# 13_-TYPEC0_PROG.net
KiCad netlist of a schematic drawn in Altium Designer
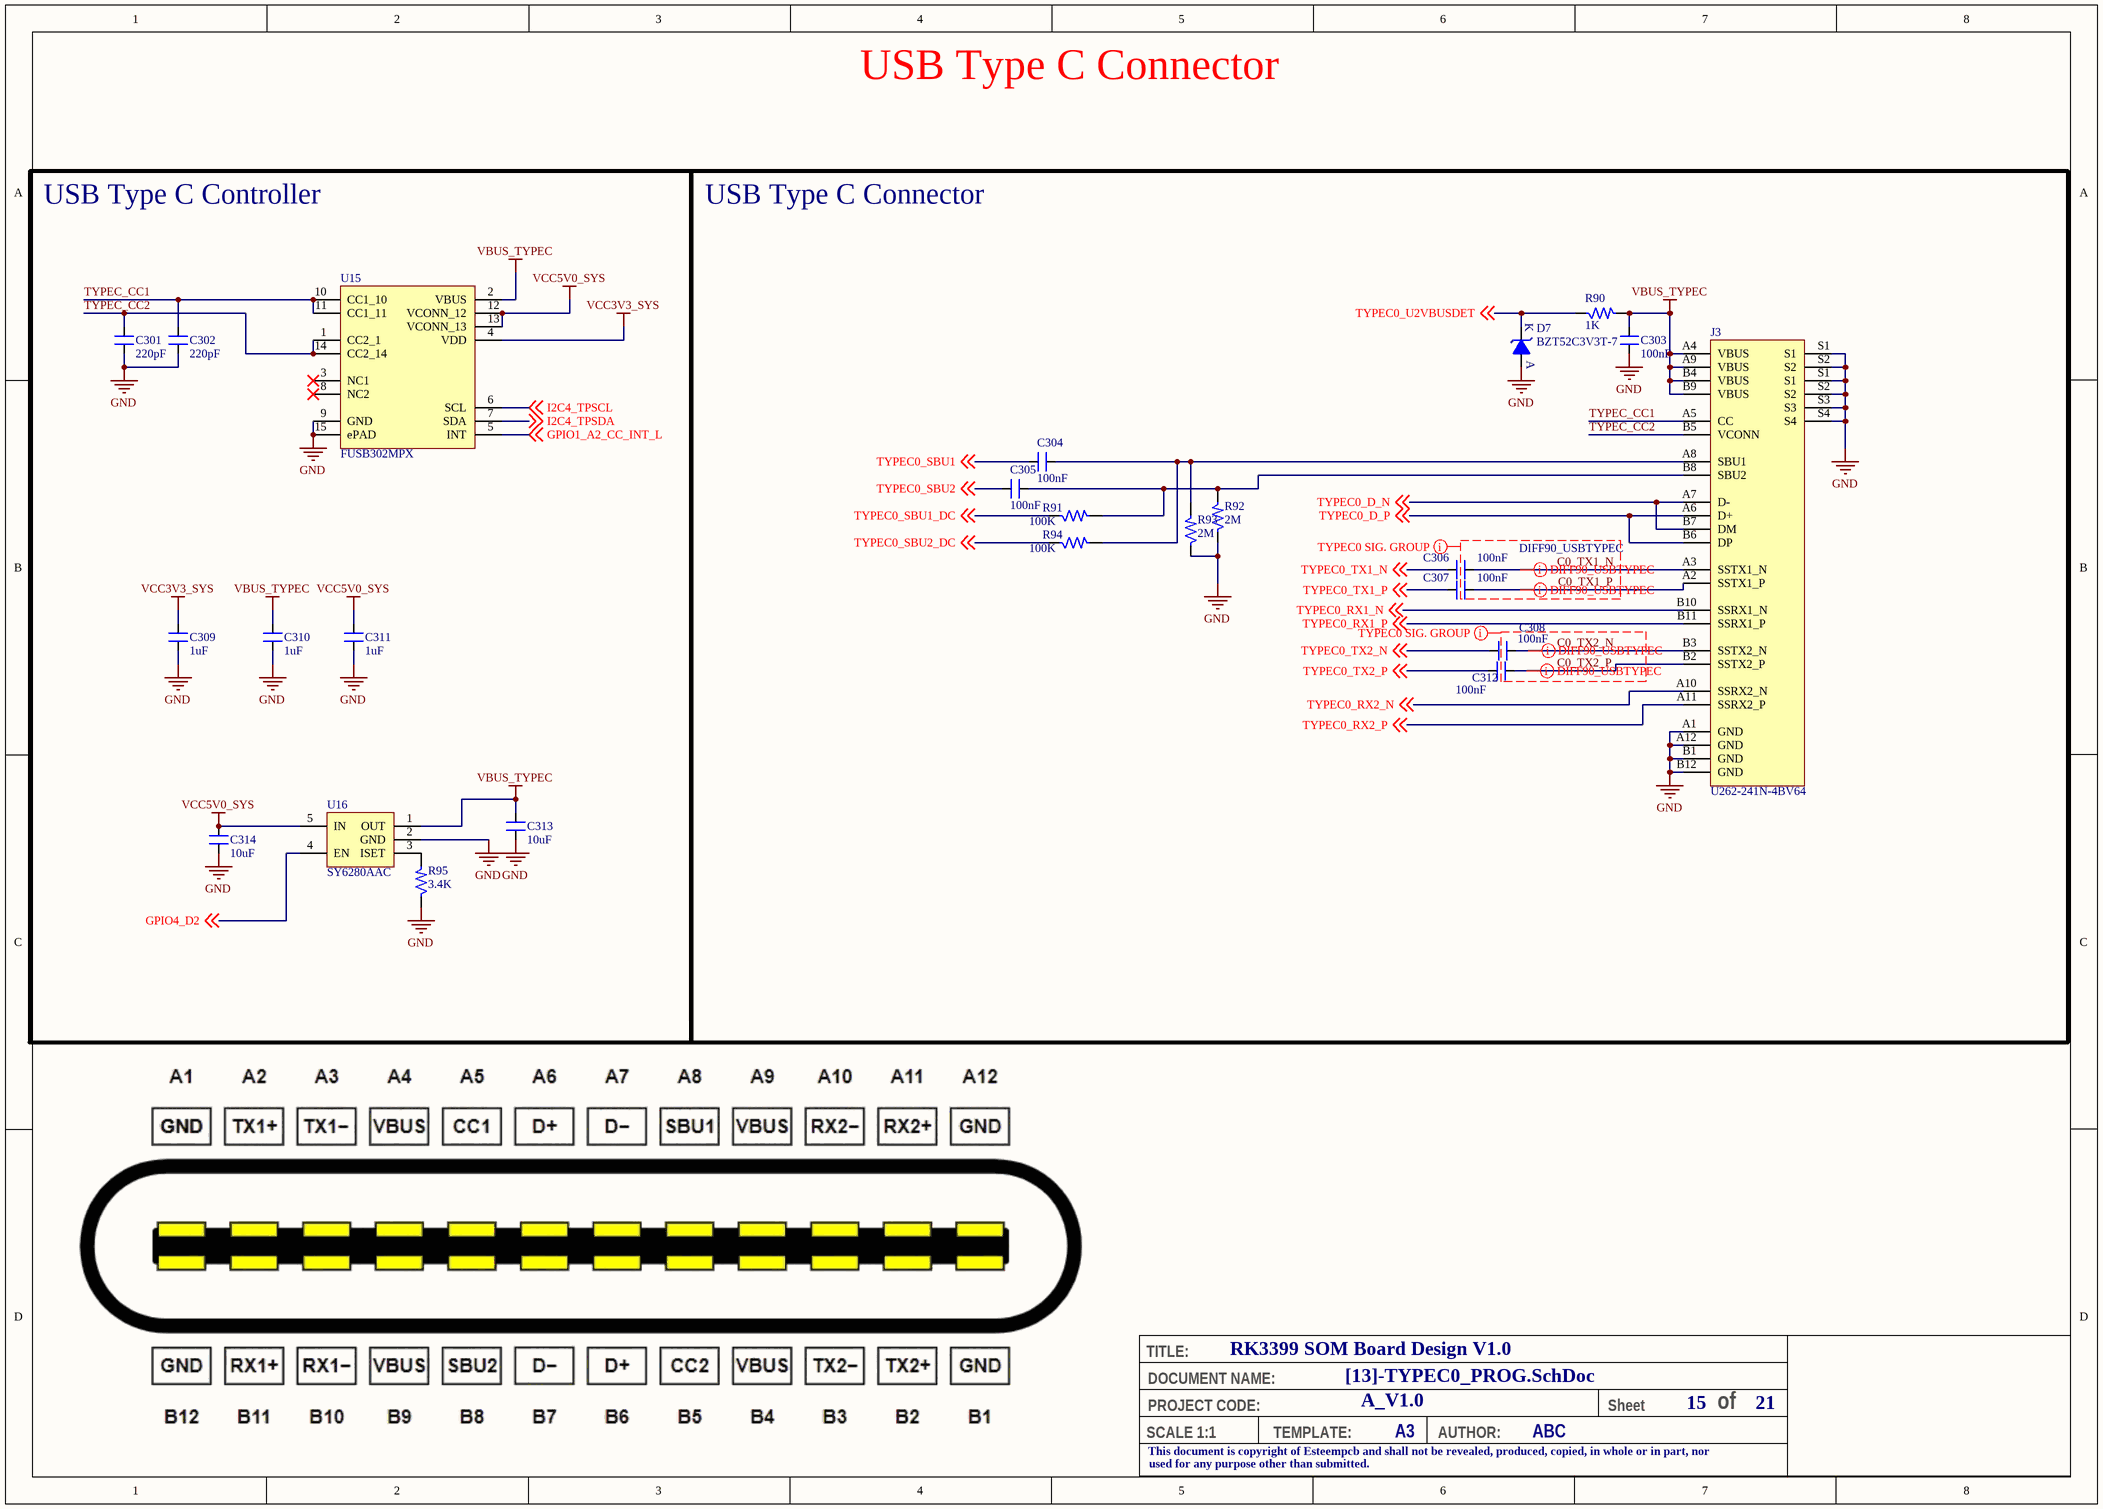
[diagram p0: [13]-TYPEC0_PROG.SchDoc]

(export (version "E")
  (design (tool "Eeschema 10.0.6"))
  (components
    (comp (ref "C301")
      (value "220pF")
      (footprint "CAP_0402")
      (description "220pF ±10% 10V Ceramic Capacitor X7R 0402 (1005 Metric)")
      (fields
        (field (name "MANUFACTURER") "KEMET")
        (field (name "MANUFACTURER PART NUMBER") "C0402C221K8RAC7867")
      )
      (libsource (lib "RK3399 _Module_Schlib") (part "CAP_220pF-10V-10%-0402"))
    )
    (comp (ref "C302")
      (value "220pF")
      (footprint "CAP_0402")
      (description "220pF ±10% 10V Ceramic Capacitor X7R 0402 (1005 Metric)")
      (fields
        (field (name "MANUFACTURER") "KEMET")
        (field (name "MANUFACTURER PART NUMBER") "C0402C221K8RAC7867")
      )
      (libsource (lib "RK3399 _Module_Schlib") (part "CAP_220pF-10V-10%-0402"))
    )
    (comp (ref "C303")
      (value "100nF")
      (footprint "CAP_0603")
      (description "0.1µF ±10% 10V Ceramic Capacitor X7R 0603 (1608 Metric)")
      (fields
        (field (name "MANUFACTURER") "Yageo")
        (field (name "MANUFACTURER PART NUMBER") "CC0603KRX7R6BB104")
      )
      (libsource (lib "RK3399 _Module_Schlib") (part "CAP_100nF-10V-5%-0603"))
    )
    (comp (ref "C304")
      (value "100nF")
      (footprint "CAP_0402")
      (description "0.1µF ±10% 25V Ceramic Capacitor X7R 0402 (1005 Metric)")
      (fields
        (field (name "MANUFACTURER") "Walsin Technology Corporation")
        (field (name "MANUFACTURER PART NUMBER") "0402B104K250CT")
      )
      (libsource (lib "RK3399 _Module_Schlib") (part "CAP_100nF-25V-10%-0402"))
    )
    (comp (ref "C305")
      (value "100nF")
      (footprint "CAP_0402")
      (description "0.1µF ±10% 25V Ceramic Capacitor X7R 0402 (1005 Metric)")
      (fields
        (field (name "MANUFACTURER") "Walsin Technology Corporation")
        (field (name "MANUFACTURER PART NUMBER") "0402B104K250CT")
      )
      (libsource (lib "RK3399 _Module_Schlib") (part "CAP_100nF-25V-10%-0402"))
    )
    (comp (ref "C306")
      (value "100nF")
      (footprint "CAP_0402")
      (description "0.1µF ±10% 25V Ceramic Capacitor X7R 0402 (1005 Metric)")
      (fields
        (field (name "MANUFACTURER") "Walsin Technology Corporation")
        (field (name "MANUFACTURER PART NUMBER") "0402B104K250CT")
      )
      (libsource (lib "RK3399 _Module_Schlib") (part "CAP_100nF-25V-10%-0402"))
    )
    (comp (ref "C307")
      (value "100nF")
      (footprint "CAP_0402")
      (description "0.1µF ±10% 25V Ceramic Capacitor X7R 0402 (1005 Metric)")
      (fields
        (field (name "MANUFACTURER") "Walsin Technology Corporation")
        (field (name "MANUFACTURER PART NUMBER") "0402B104K250CT")
      )
      (libsource (lib "RK3399 _Module_Schlib") (part "CAP_100nF-25V-10%-0402"))
    )
    (comp (ref "C308")
      (value "100nF")
      (footprint "CAP_0402")
      (description "0.1µF ±10% 25V Ceramic Capacitor X7R 0402 (1005 Metric)")
      (fields
        (field (name "MANUFACTURER") "Walsin Technology Corporation")
        (field (name "MANUFACTURER PART NUMBER") "0402B104K250CT")
      )
      (libsource (lib "RK3399 _Module_Schlib") (part "CAP_100nF-25V-10%-0402"))
    )
    (comp (ref "C309")
      (value "1uF")
      (footprint "CAP_0402")
      (description "1µF ±10% 10V Ceramic Capacitor X6S 0402 (1005 Metric)")
      (fields
        (field (name "MANUFACTURER") "Murata Electronics")
        (field (name "MANUFACTURER PART NUMBER") "GRT155C81A105KE01D")
      )
      (libsource (lib "RK3399 _Module_Schlib") (part "CAP_1uF-10V-10%-0402"))
    )
    (comp (ref "C310")
      (value "1uF")
      (footprint "CAP_0402")
      (description "1µF ±10% 10V Ceramic Capacitor X6S 0402 (1005 Metric)")
      (fields
        (field (name "MANUFACTURER") "Murata Electronics")
        (field (name "MANUFACTURER PART NUMBER") "GRT155C81A105KE01D")
      )
      (libsource (lib "RK3399 _Module_Schlib") (part "CAP_1uF-10V-10%-0402"))
    )
    (comp (ref "C311")
      (value "1uF")
      (footprint "CAP_0402")
      (description "1µF ±10% 10V Ceramic Capacitor X6S 0402 (1005 Metric)")
      (fields
        (field (name "MANUFACTURER") "Murata Electronics")
        (field (name "MANUFACTURER PART NUMBER") "GRT155C81A105KE01D")
      )
      (libsource (lib "RK3399 _Module_Schlib") (part "CAP_1uF-10V-10%-0402"))
    )
    (comp (ref "C312")
      (value "100nF")
      (footprint "CAP_0402")
      (description "0.1µF ±10% 25V Ceramic Capacitor X7R 0402 (1005 Metric)")
      (fields
        (field (name "MANUFACTURER") "Walsin Technology Corporation")
        (field (name "MANUFACTURER PART NUMBER") "0402B104K250CT")
      )
      (libsource (lib "RK3399 _Module_Schlib") (part "CAP_100nF-25V-10%-0402"))
    )
    (comp (ref "C313")
      (value "10uF")
      (footprint "CAP_0402")
      (description "10µF ±20% 10V Ceramic Capacitor X5R 0402 (1005 Metric)")
      (fields
        (field (name "MANUFACTURER PART NUMBER") "CL05A106MP5NUNC")
        (field (name "MANUFACTURER") "Samsung Electro-Mechanics")
      )
      (libsource (lib "RK3399 _Module_Schlib") (part "CAP_10uF-10V-20%-0402"))
    )
    (comp (ref "C314")
      (value "10uF")
      (footprint "CAP_0402")
      (description "10µF ±20% 10V Ceramic Capacitor X5R 0402 (1005 Metric)")
      (fields
        (field (name "MANUFACTURER PART NUMBER") "CL05A106MP5NUNC")
        (field (name "MANUFACTURER") "Samsung Electro-Mechanics")
      )
      (libsource (lib "RK3399 _Module_Schlib") (part "CAP_10uF-10V-20%-0402"))
    )
    (comp (ref "D7")
      (value "BZT52C3V3T-7")
      (footprint "DIO_SOD523")
      (description "Zener Diode 3.3V 300mW ±6% Surface Mount SOD-523")
      (fields (field (name "MANUFACTURER") "Diodes Incorporated"))
      (libsource (lib "RK3399 _Module_Schlib") (part "DIO-Z_3.3V-300mW-SOD-523"))
    )
    (comp (ref "J3")
      (value "U262-241N-4BV64")
      (footprint "CON24_19.64_U262-241N-4BV64_TH_RA")
      (description "USB - Type C Female 24 SMD USB Connectors RoHS")
      (fields (field (name "MANUFACTURER") "XKB Connectivity"))
      (libsource (lib "RK3399 _Module_Schlib") (part "CON-TYPEC_U262-241N-4BV64-SMD"))
    )
    (comp (ref "R90")
      (value "1K")
      (footprint "RES_0402")
      (description "1 kOhms ±1% 0.1W, 1/10W Chip Resistor 0402 (1005 Metric) Anti-Sulfur Thin Film")
      (fields
        (field (name "MANUFACTURER") "Vishay Beyschlag/Draloric/BC Components")
        (field (name "MANUFACTURER PART NUMBER") "MCS04020C1001FE000")
      )
      (libsource (lib "RK3399 _Module_Schlib") (part "RES_1K-0.1W-1%-0402"))
    )
    (comp (ref "R91")
      (value "100K")
      (footprint "RES_0402")
      (description "100 kOhms ±1% 0.1W, 1/10W Chip Resistor 0402 (1005 Metric) Anti-Sulfur Thin Film")
      (fields
        (field (name "MANUFACTURER") "Vishay Beyschlag/Draloric/BC Components")
        (field (name "MANUFACTURER PART NUMBER") "MCS04020C1003FE000")
      )
      (libsource (lib "RK3399 _Module_Schlib") (part "RES_100K-0.1W-1%-0402"))
    )
    (comp (ref "R92")
      (value "2M")
      (footprint "RES_0402")
      (description "2 MOhms ±1% 0.1W, 1/10W Chip Resistor 0402 (1005 Metric) Anti-Sulfur Thin Film")
      (fields
        (field (name "MANUFACTURER") "Vishay Beyschlag/Draloric/BC Components")
        (field (name "MANUFACTURER PART NUMBER") "MCS04020C2004FE000")
      )
      (libsource (lib "RK3399 _Module_Schlib") (part "RES_2M-0.1W-1%-0402"))
    )
    (comp (ref "R93")
      (value "2M")
      (footprint "RES_0402")
      (description "2 MOhms ±1% 0.1W, 1/10W Chip Resistor 0402 (1005 Metric) Anti-Sulfur Thin Film")
      (fields
        (field (name "MANUFACTURER") "Vishay Beyschlag/Draloric/BC Components")
        (field (name "MANUFACTURER PART NUMBER") "MCS04020C2004FE000")
      )
      (libsource (lib "RK3399 _Module_Schlib") (part "RES_2M-0.1W-1%-0402"))
    )
    (comp (ref "R94")
      (value "100K")
      (footprint "RES_0402")
      (description "100 kOhms ±1% 0.1W, 1/10W Chip Resistor 0402 (1005 Metric) Anti-Sulfur Thin Film")
      (fields
        (field (name "MANUFACTURER") "Vishay Beyschlag/Draloric/BC Components")
        (field (name "MANUFACTURER PART NUMBER") "MCS04020C1003FE000")
      )
      (libsource (lib "RK3399 _Module_Schlib") (part "RES_100K-0.1W-1%-0402"))
    )
    (comp (ref "R95")
      (value "3.4K")
      (footprint "RES_0402")
      (description "3.4 kOhms ±1% 0.1W, 1/10W Chip Resistor 0402 (1005 Metric) Automotive AEC-Q200 Thick Film")
      (fields
        (field (name "MANUFACTURER") "Panasonic Electronic Components")
        (field (name "MANUFACTURER PART NUMBER") "ERJ-2RKF3401X")
      )
      (libsource (lib "RK3399 _Module_Schlib") (part "RES_3.4K-0.1W-1%-0402"))
    )
    (comp (ref "U15")
      (value "FUSB302MPX")
      (footprint "MLP-14_98.4X98.4_SMD")
      (description "USB Controller USB 3.1 USB Interface 14-MLP (2.5x2.5)")
      (fields (field (name "MANUFACTURER") "ON Semiconductor"))
      (libsource (lib "RK3399 _Module_Schlib") (part "IC_FUSB302MPX"))
    )
    (comp (ref "U16")
      (value "SY6280AAC")
      (footprint "SOT23-5")
      (description "SOT-23-5 PMIC - Power Distribution Switches RoHS")
      (fields (field (name "MANUFACTURER") "Silergy Corp"))
      (libsource (lib "RK3399 _Module_Schlib") (part "REG-ADJ_5.5V-5.5V-1.25A-SOT-23-5"))
    )
  )
  (nets
    (net (code "1") (name "/C0_TX1_N") (class "Default")
      (node (ref "C306") (pin "2") (pinfunction "2_2") (pintype "passive"))
      (node (ref "J3") (pin "A3") (pinfunction "SSTX1_N_A3") (pintype "passive"))
    )
    (net (code "2") (name "/C0_TX1_P") (class "Default")
      (node (ref "C307") (pin "2") (pinfunction "2_2") (pintype "passive"))
      (node (ref "J3") (pin "A2") (pinfunction "SSTX1_P_A2") (pintype "passive"))
    )
    (net (code "3") (name "/C0_TX2_N") (class "Default")
      (node (ref "C308") (pin "2") (pinfunction "2_2") (pintype "passive"))
      (node (ref "J3") (pin "B3") (pinfunction "SSTX2_N_B3") (pintype "passive"))
    )
    (net (code "4") (name "/C0_TX2_P") (class "Default")
      (node (ref "C312") (pin "2") (pinfunction "2_2") (pintype "passive"))
      (node (ref "J3") (pin "B2") (pinfunction "SSTX2_P_B2") (pintype "passive"))
    )
    (net (code "5") (name "/TYPEC_CC1") (class "Default")
      (node (ref "C302") (pin "2") (pinfunction "2_2") (pintype "passive"))
      (node (ref "J3") (pin "A5") (pinfunction "CC_A5") (pintype "passive"))
      (node (ref "U15") (pin "10") (pinfunction "CC1_10_10") (pintype "passive"))
      (node (ref "U15") (pin "11") (pinfunction "CC1_11_11") (pintype "passive"))
    )
    (net (code "6") (name "/TYPEC_CC2") (class "Default")
      (node (ref "C301") (pin "2") (pinfunction "2_2") (pintype "passive"))
      (node (ref "J3") (pin "B5") (pinfunction "VCONN_B5") (pintype "passive"))
      (node (ref "U15") (pin "1") (pinfunction "CC2_1_1") (pintype "passive"))
      (node (ref "U15") (pin "14") (pinfunction "CC2_14_14") (pintype "passive"))
    )
    (net (code "7") (name "GND") (class "Default")
      (node (ref "C301") (pin "1") (pinfunction "1_1") (pintype "passive"))
      (node (ref "C302") (pin "1") (pinfunction "1_1") (pintype "passive"))
      (node (ref "C303") (pin "1") (pinfunction "1_1") (pintype "passive"))
      (node (ref "C309") (pin "1") (pinfunction "1_1") (pintype "passive"))
      (node (ref "C310") (pin "1") (pinfunction "1_1") (pintype "passive"))
      (node (ref "C311") (pin "1") (pinfunction "1_1") (pintype "passive"))
      (node (ref "C313") (pin "1") (pinfunction "1_1") (pintype "passive"))
      (node (ref "C314") (pin "1") (pinfunction "1_1") (pintype "passive"))
      (node (ref "D7") (pin "A") (pinfunction "A_A") (pintype "passive"))
      (node (ref "J3") (pin "A1") (pinfunction "GND_A1") (pintype "passive"))
      (node (ref "J3") (pin "A12") (pinfunction "GND_A12") (pintype "passive"))
      (node (ref "J3") (pin "B1") (pinfunction "GND_B1") (pintype "passive"))
      (node (ref "J3") (pin "B12") (pinfunction "GND_B12") (pintype "passive"))
      (node (ref "J3") (pin "S1") (pinfunction "S1_S1") (pintype "passive"))
      (node (ref "J3") (pin "S2") (pinfunction "S2_S2") (pintype "passive"))
      (node (ref "J3") (pin "S3") (pinfunction "S3_S3") (pintype "passive"))
      (node (ref "J3") (pin "S4") (pinfunction "S4_S4") (pintype "passive"))
      (node (ref "R92") (pin "1") (pinfunction "1_1") (pintype "passive"))
      (node (ref "R93") (pin "1") (pinfunction "1_1") (pintype "passive"))
      (node (ref "R95") (pin "1") (pinfunction "1_1") (pintype "passive"))
      (node (ref "U15") (pin "15") (pinfunction "ePAD_15") (pintype "passive"))
      (node (ref "U15") (pin "9") (pinfunction "GND_9") (pintype "passive"))
      (node (ref "U16") (pin "2") (pinfunction "GND_2") (pintype "passive"))
    )
    (net (code "8") (name "GPIO1_A2_CC_INT_L") (class "Default")
      (node (ref "U15") (pin "5") (pinfunction "INT_5") (pintype "passive"))
    )
    (net (code "9") (name "GPIO4_D2") (class "Default")
      (node (ref "U16") (pin "4") (pinfunction "EN_4") (pintype "passive"))
    )
    (net (code "10") (name "I2C4_TPSCL") (class "Default")
      (node (ref "U15") (pin "6") (pinfunction "SCL_6") (pintype "passive"))
    )
    (net (code "11") (name "I2C4_TPSDA") (class "Default")
      (node (ref "U15") (pin "7") (pinfunction "SDA_7") (pintype "passive"))
    )
    (net (code "12") (name "Net-(J3-SBU1)") (class "Default")
      (node (ref "C304") (pin "2") (pinfunction "2_2") (pintype "passive"))
      (node (ref "J3") (pin "A8") (pinfunction "SBU1_A8") (pintype "passive"))
      (node (ref "R93") (pin "2") (pinfunction "2_2") (pintype "passive"))
      (node (ref "R94") (pin "2") (pinfunction "2_2") (pintype "passive"))
    )
    (net (code "13") (name "Net-(J3-SBU2)") (class "Default")
      (node (ref "C305") (pin "2") (pinfunction "2_2") (pintype "passive"))
      (node (ref "J3") (pin "B8") (pinfunction "SBU2_B8") (pintype "passive"))
      (node (ref "R91") (pin "2") (pinfunction "2_2") (pintype "passive"))
      (node (ref "R92") (pin "2") (pinfunction "2_2") (pintype "passive"))
    )
    (net (code "14") (name "Net-(U16-ISET)") (class "Default")
      (node (ref "R95") (pin "2") (pinfunction "2_2") (pintype "passive"))
      (node (ref "U16") (pin "3") (pinfunction "ISET_3") (pintype "passive"))
    )
    (net (code "15") (name "TYPEC0_D_N") (class "Default")
      (node (ref "J3") (pin "A7") (pinfunction "D-_A7") (pintype "passive"))
      (node (ref "J3") (pin "B7") (pinfunction "DM_B7") (pintype "passive"))
    )
    (net (code "16") (name "TYPEC0_D_P") (class "Default")
      (node (ref "J3") (pin "A6") (pinfunction "D+_A6") (pintype "passive"))
      (node (ref "J3") (pin "B6") (pinfunction "DP_B6") (pintype "passive"))
    )
    (net (code "17") (name "TYPEC0_RX1_N") (class "Default")
      (node (ref "J3") (pin "B10") (pinfunction "SSRX1_N_B10") (pintype "passive"))
    )
    (net (code "18") (name "TYPEC0_RX1_P") (class "Default")
      (node (ref "J3") (pin "B11") (pinfunction "SSRX1_P_B11") (pintype "passive"))
    )
    (net (code "19") (name "TYPEC0_RX2_N") (class "Default")
      (node (ref "J3") (pin "A10") (pinfunction "SSRX2_N_A10") (pintype "passive"))
    )
    (net (code "20") (name "TYPEC0_RX2_P") (class "Default")
      (node (ref "J3") (pin "A11") (pinfunction "SSRX2_P_A11") (pintype "passive"))
    )
    (net (code "21") (name "TYPEC0_SBU1") (class "Default")
      (node (ref "C304") (pin "1") (pinfunction "1_1") (pintype "passive"))
    )
    (net (code "22") (name "TYPEC0_SBU1_DC") (class "Default")
      (node (ref "R91") (pin "1") (pinfunction "1_1") (pintype "passive"))
    )
    (net (code "23") (name "TYPEC0_SBU2") (class "Default")
      (node (ref "C305") (pin "1") (pinfunction "1_1") (pintype "passive"))
    )
    (net (code "24") (name "TYPEC0_SBU2_DC") (class "Default")
      (node (ref "R94") (pin "1") (pinfunction "1_1") (pintype "passive"))
    )
    (net (code "25") (name "TYPEC0_TX1_N") (class "Default")
      (node (ref "C306") (pin "1") (pinfunction "1_1") (pintype "passive"))
    )
    (net (code "26") (name "TYPEC0_TX1_P") (class "Default")
      (node (ref "C307") (pin "1") (pinfunction "1_1") (pintype "passive"))
    )
    (net (code "27") (name "TYPEC0_TX2_N") (class "Default")
      (node (ref "C308") (pin "1") (pinfunction "1_1") (pintype "passive"))
    )
    (net (code "28") (name "TYPEC0_TX2_P") (class "Default")
      (node (ref "C312") (pin "1") (pinfunction "1_1") (pintype "passive"))
    )
    (net (code "29") (name "TYPEC0_U2VBUSDET") (class "Default")
      (node (ref "D7") (pin "K") (pinfunction "K_K") (pintype "passive"))
      (node (ref "R90") (pin "1") (pinfunction "1_1") (pintype "passive"))
    )
    (net (code "30") (name "VBUS_TYPEC") (class "Default")
      (node (ref "C303") (pin "2") (pinfunction "2_2") (pintype "passive"))
      (node (ref "C310") (pin "2") (pinfunction "2_2") (pintype "passive"))
      (node (ref "C313") (pin "2") (pinfunction "2_2") (pintype "passive"))
      (node (ref "J3") (pin "A4") (pinfunction "VBUS_A4") (pintype "passive"))
      (node (ref "J3") (pin "A9") (pinfunction "VBUS_A9") (pintype "passive"))
      (node (ref "J3") (pin "B4") (pinfunction "VBUS_B4") (pintype "passive"))
      (node (ref "J3") (pin "B9") (pinfunction "VBUS_B9") (pintype "passive"))
      (node (ref "R90") (pin "2") (pinfunction "2_2") (pintype "passive"))
      (node (ref "U15") (pin "2") (pinfunction "VBUS_2") (pintype "passive"))
      (node (ref "U16") (pin "1") (pinfunction "OUT_1") (pintype "passive"))
    )
    (net (code "31") (name "VCC3V3_SYS") (class "Default")
      (node (ref "C309") (pin "2") (pinfunction "2_2") (pintype "passive"))
      (node (ref "U15") (pin "4") (pinfunction "VDD_4") (pintype "passive"))
    )
    (net (code "32") (name "VCC5V0_SYS") (class "Default")
      (node (ref "C311") (pin "2") (pinfunction "2_2") (pintype "passive"))
      (node (ref "C314") (pin "2") (pinfunction "2_2") (pintype "passive"))
      (node (ref "U15") (pin "12") (pinfunction "VCONN_12_12") (pintype "passive"))
      (node (ref "U15") (pin "13") (pinfunction "VCONN_13_13") (pintype "passive"))
      (node (ref "U16") (pin "5") (pinfunction "IN_5") (pintype "passive"))
    )
    (net (code "33") (name "unconnected-(U15-NC1-Pad3)") (class "Default")
      (node (ref "U15") (pin "3") (pinfunction "NC1_3") (pintype "passive+no_connect"))
    )
    (net (code "34") (name "unconnected-(U15-NC2-Pad8)") (class "Default")
      (node (ref "U15") (pin "8") (pinfunction "NC2_8") (pintype "passive+no_connect"))
    )
  )
)
